# ModulCentralny.net
KiCad netlist of a schematic drawn in EAGLE
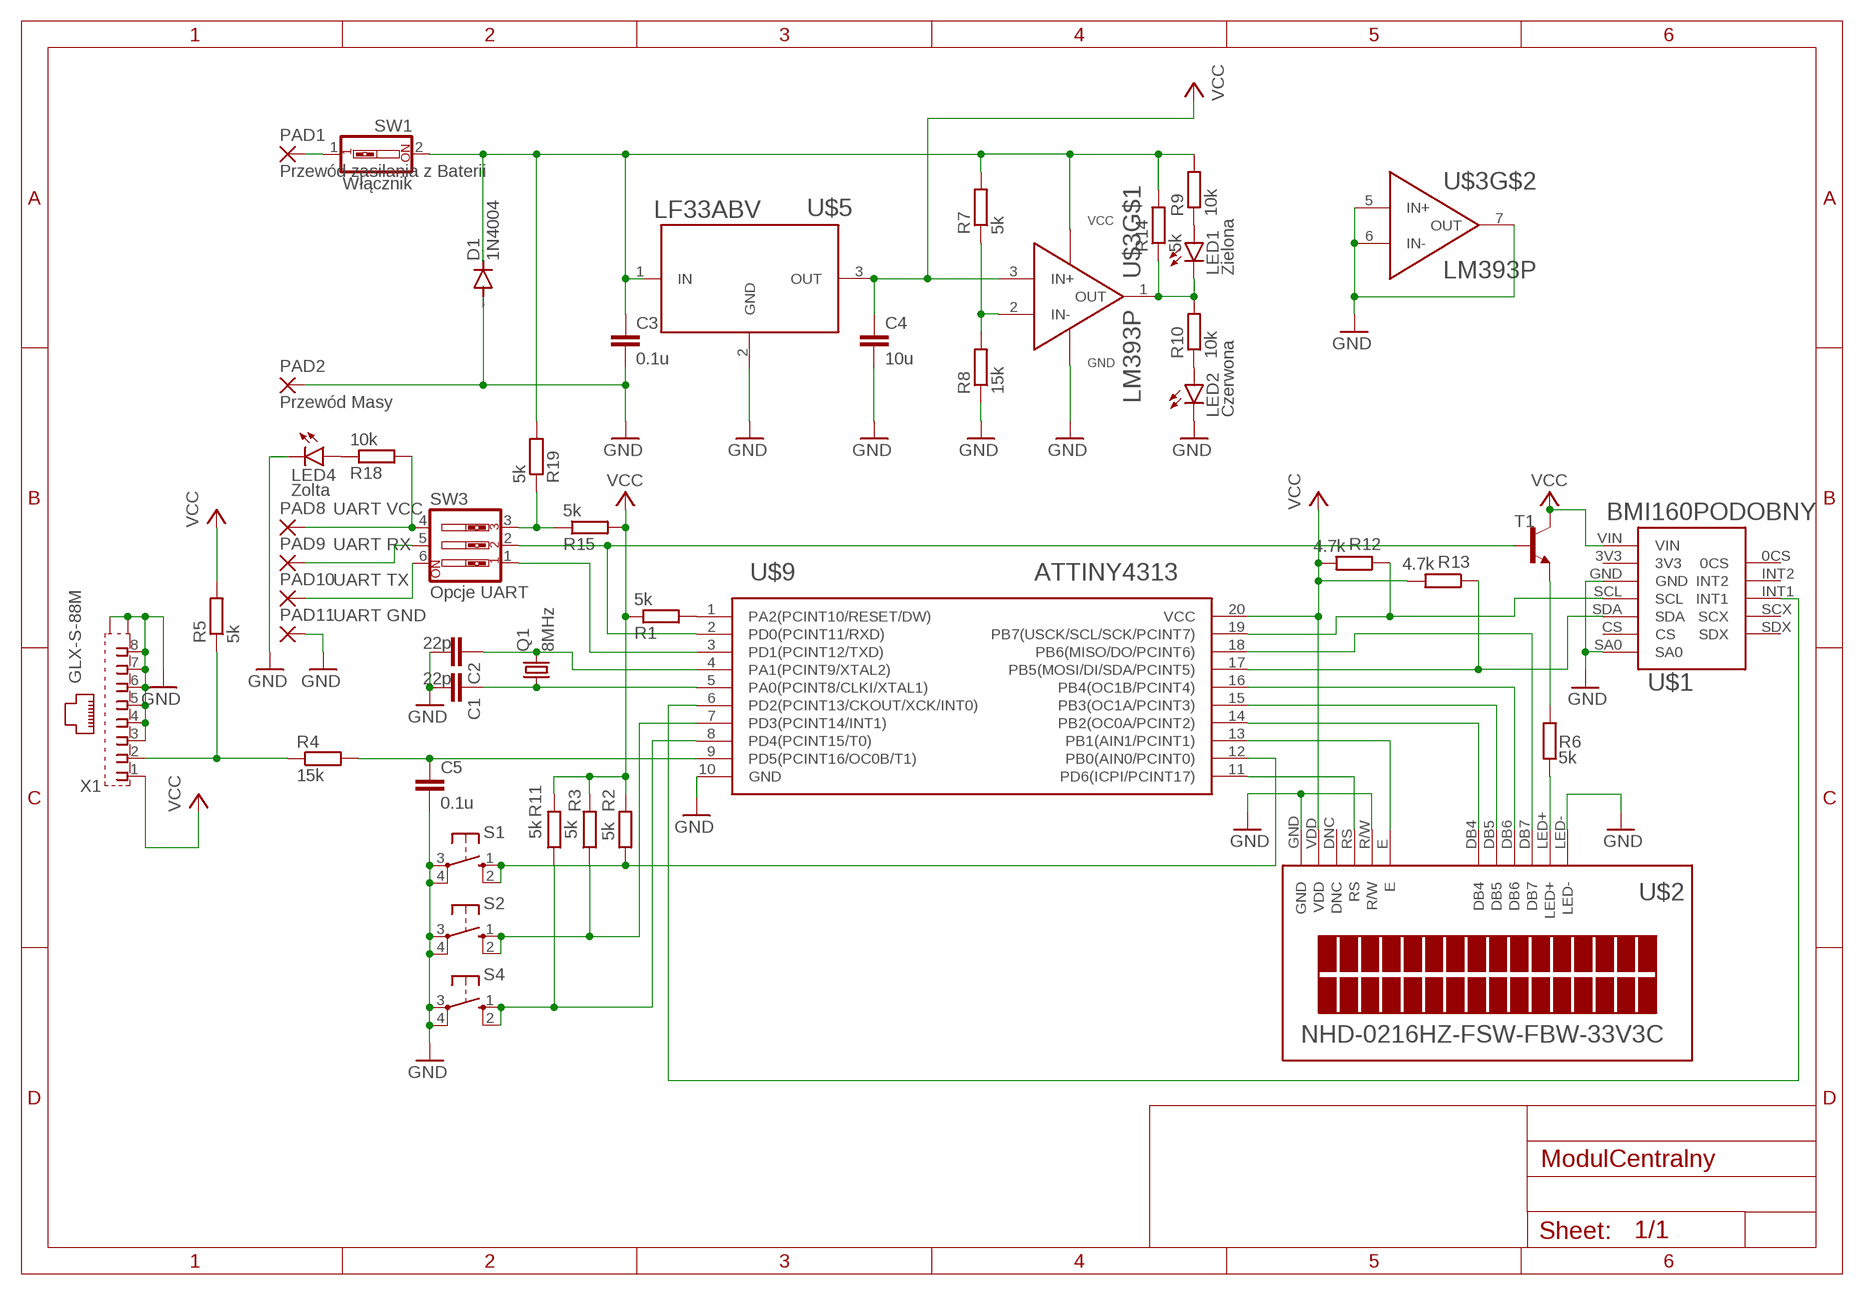
[diagram p0: schematic, sheet 1]

(export (version "E")
  (design (tool "Eeschema 10.0.6"))
  (components
    (comp (ref "C1")
      (value "22p")
      (footprint "eagle-import:C2.5-3")
      (libsource (lib "eagle-import") (part "C2,5-3"))
    )
    (comp (ref "C2")
      (value "22p")
      (footprint "eagle-import:C2.5-3")
      (libsource (lib "eagle-import") (part "C2,5-3"))
    )
    (comp (ref "C3")
      (value "0.1u")
      (footprint "eagle-import:C2.5-3")
      (libsource (lib "eagle-import") (part "C2,5-3"))
    )
    (comp (ref "C4")
      (value "10u")
      (footprint "eagle-import:C2.5-3")
      (libsource (lib "eagle-import") (part "C2,5-3"))
    )
    (comp (ref "C5")
      (value "0.1u")
      (footprint "eagle-import:C2.5-3")
      (libsource (lib "eagle-import") (part "C2,5-3"))
    )
    (comp (ref "D1")
      (value "1N4004")
      (footprint "eagle-import:DO41-10")
      (libsource (lib "eagle-import") (part "1N4004"))
    )
    (comp (ref "LED1")
      (value "Zielona")
      (footprint "eagle-import:LED5MM")
      (libsource (lib "eagle-import") (part "LED5MM"))
    )
    (comp (ref "LED2")
      (value "Czerwona")
      (footprint "eagle-import:LED5MM")
      (libsource (lib "eagle-import") (part "LED5MM"))
    )
    (comp (ref "LED4")
      (value "Zolta")
      (footprint "eagle-import:LED5MM")
      (libsource (lib "eagle-import") (part "LED5MM"))
    )
    (comp (ref "PAD1")
      (value "Przewód zasilania z Baterii")
      (footprint "eagle-import:2,54_1,1")
      (libsource (lib "eagle-import") (part "WIREPAD2,54/1,1"))
    )
    (comp (ref "PAD2")
      (value "Przewód Masy")
      (footprint "eagle-import:2,54_1,1")
      (libsource (lib "eagle-import") (part "WIREPAD2,54/1,1"))
    )
    (comp (ref "PAD8")
      (value "UART VCC")
      (footprint "eagle-import:3,17_1,3")
      (libsource (lib "eagle-import") (part "WIREPAD3,17/1,3"))
    )
    (comp (ref "PAD9")
      (value "UART RX")
      (footprint "eagle-import:3,17_1,3")
      (libsource (lib "eagle-import") (part "WIREPAD3,17/1,3"))
    )
    (comp (ref "PAD10")
      (value "UART TX")
      (footprint "eagle-import:3,17_1,3")
      (libsource (lib "eagle-import") (part "WIREPAD3,17/1,3"))
    )
    (comp (ref "PAD11")
      (value "UART GND")
      (footprint "eagle-import:3,17_1,3")
      (libsource (lib "eagle-import") (part "WIREPAD3,17/1,3"))
    )
    (comp (ref "Q1")
      (value "8MHz")
      (footprint "eagle-import:HC49U70")
      (libsource (lib "eagle-import") (part "CRYSTALHC49U70"))
    )
    (comp (ref "R1")
      (value "5k")
      (footprint "eagle-import:0207_7")
      (libsource (lib "eagle-import") (part "R-EU_0207/7"))
    )
    (comp (ref "R2")
      (value "5k")
      (footprint "eagle-import:0207_7")
      (libsource (lib "eagle-import") (part "R-EU_0207/7"))
    )
    (comp (ref "R3")
      (value "5k")
      (footprint "eagle-import:0207_7")
      (libsource (lib "eagle-import") (part "R-EU_0207/7"))
    )
    (comp (ref "R4")
      (value "15k")
      (footprint "eagle-import:0207_7")
      (libsource (lib "eagle-import") (part "R-EU_0207/7"))
    )
    (comp (ref "R5")
      (value "5k")
      (footprint "eagle-import:0207_7")
      (libsource (lib "eagle-import") (part "R-EU_0207/7"))
    )
    (comp (ref "R6")
      (value "5k")
      (footprint "eagle-import:0207_7")
      (libsource (lib "eagle-import") (part "R-EU_0207/7"))
    )
    (comp (ref "R7")
      (value "5k")
      (footprint "eagle-import:0207_7")
      (libsource (lib "eagle-import") (part "R-EU_0207/7"))
    )
    (comp (ref "R8")
      (value "15k")
      (footprint "eagle-import:0207_7")
      (libsource (lib "eagle-import") (part "R-EU_0207/7"))
    )
    (comp (ref "R9")
      (value "10k")
      (footprint "eagle-import:0207_7")
      (libsource (lib "eagle-import") (part "R-EU_0207/7"))
    )
    (comp (ref "R10")
      (value "10k")
      (footprint "eagle-import:0207_7")
      (libsource (lib "eagle-import") (part "R-EU_0207/7"))
    )
    (comp (ref "R11")
      (value "5k")
      (footprint "eagle-import:0207_7")
      (libsource (lib "eagle-import") (part "R-EU_0207/7"))
    )
    (comp (ref "R12")
      (value "4.7k")
      (footprint "eagle-import:0207_7")
      (libsource (lib "eagle-import") (part "R-EU_0207/7"))
    )
    (comp (ref "R13")
      (value "4.7k")
      (footprint "eagle-import:0207_7")
      (libsource (lib "eagle-import") (part "R-EU_0207/7"))
    )
    (comp (ref "R14")
      (value "5k")
      (footprint "eagle-import:0207_7")
      (libsource (lib "eagle-import") (part "R-EU_0207/7"))
    )
    (comp (ref "R15")
      (value "5k")
      (footprint "eagle-import:0207_7")
      (libsource (lib "eagle-import") (part "R-EU_0207/7"))
    )
    (comp (ref "R18")
      (value "10k")
      (footprint "eagle-import:0207_7")
      (libsource (lib "eagle-import") (part "R-EU_0207/7"))
    )
    (comp (ref "R19")
      (value "5k")
      (footprint "eagle-import:0207_7")
      (libsource (lib "eagle-import") (part "R-EU_0207/7"))
    )
    (comp (ref "S1")
      (value "10-XX")
      (footprint "eagle-import:B3F-10XX")
      (fields (field (name "MPN") "B3F-1000"))
      (libsource (lib "eagle-import") (part "10-XX"))
    )
    (comp (ref "S2")
      (value "10-XX")
      (footprint "eagle-import:B3F-10XX")
      (fields (field (name "MPN") "B3F-1000"))
      (libsource (lib "eagle-import") (part "10-XX"))
    )
    (comp (ref "S4")
      (value "10-XX")
      (footprint "eagle-import:B3F-10XX")
      (fields (field (name "MPN") "B3F-1000"))
      (libsource (lib "eagle-import") (part "10-XX"))
    )
    (comp (ref "SW1")
      (value "Włącznik")
      (footprint "eagle-import:EDG-01")
      (libsource (lib "eagle-import") (part "SW_DIP-1"))
    )
    (comp (ref "SW3")
      (value "Opcje UART")
      (footprint "eagle-import:EDG-03")
      (libsource (lib "eagle-import") (part "SW_DIP-3"))
    )
    (comp (ref "T1")
      (value "BC547B-NPN-TO92-CBE")
      (footprint "eagle-import:TO92-CBE")
      (libsource (lib "eagle-import") (part "-NPN-TO92-CBEBC547B"))
    )
    (comp (ref "U$1")
      (value "BMI160PODOBNY")
      (footprint "eagle-import:BMI160MODULE")
      (libsource (lib "eagle-import") (part "BMI160PODOBNY"))
    )
    (comp (ref "U$2")
      (value "NHD-0216HZ-FSW-FBW-33V3C")
      (footprint "eagle-import:NHD-0216HZ-FSW-FBW-33V3C")
      (libsource (lib "eagle-import") (part "NHD-0216HZ-FSW-FBW-33V3C"))
    )
    (comp (ref "U$3")
      (value "LM393P")
      (footprint "eagle-import:R-PDIP-T8")
      (libsource (lib "eagle-import") (part "LM393P"))
    )
    (comp (ref "U$5")
      (value "LF33ABV")
      (footprint "eagle-import:TO-220")
      (libsource (lib "eagle-import") (part "LF33ABV"))
    )
    (comp (ref "U$9")
      (value "ATTINY4313")
      (footprint "eagle-import:20P3")
      (libsource (lib "eagle-import") (part "ATTINY4313"))
    )
    (comp (ref "X1")
      (value "GLX-S-88M")
      (footprint "eagle-import:GLX-S-88M")
      (libsource (lib "eagle-import") (part "GLX-S-88M"))
    )
  )
  (nets
    (net (code "1") (name "GND") (class "Default")
      (node (ref "C1") (pin "2") (pinfunction "2_2") (pintype "passive"))
      (node (ref "C2") (pin "2") (pinfunction "2_2") (pintype "passive"))
      (node (ref "C3") (pin "2") (pinfunction "2_2") (pintype "passive"))
      (node (ref "C4") (pin "2") (pinfunction "2_2") (pintype "passive"))
      (node (ref "C5") (pin "2") (pinfunction "2_2") (pintype "passive"))
      (node (ref "D1") (pin "A") (pinfunction "A_A") (pintype "passive"))
      (node (ref "LED2") (pin "K") (pinfunction "C_K") (pintype "passive"))
      (node (ref "LED4") (pin "K") (pinfunction "C_K") (pintype "passive"))
      (node (ref "PAD11") (pin "1") (pinfunction "P_1") (pintype "passive"))
      (node (ref "PAD2") (pin "1") (pinfunction "P_1") (pintype "passive"))
      (node (ref "R8") (pin "1") (pinfunction "1_1") (pintype "passive"))
      (node (ref "S1") (pin "3") (pinfunction "P_3") (pintype "passive"))
      (node (ref "S1") (pin "4") (pinfunction "P1_4") (pintype "passive"))
      (node (ref "S2") (pin "3") (pinfunction "P_3") (pintype "passive"))
      (node (ref "S2") (pin "4") (pinfunction "P1_4") (pintype "passive"))
      (node (ref "S4") (pin "3") (pinfunction "P_3") (pintype "passive"))
      (node (ref "S4") (pin "4") (pinfunction "P1_4") (pintype "passive"))
      (node (ref "U$1") (pin "GND") (pinfunction "GND_GND") (pintype "bidirectional"))
      (node (ref "U$1") (pin "SA0") (pinfunction "SA0_SA0") (pintype "bidirectional"))
      (node (ref "U$2") (pin "GND") (pinfunction "GND_GND") (pintype "bidirectional"))
      (node (ref "U$2") (pin "LED-") (pinfunction "LED-_LED-") (pintype "bidirectional"))
      (node (ref "U$2") (pin "R/W") (pinfunction "R/W_R/W") (pintype "bidirectional"))
      (node (ref "U$3") (pin "4") (pinfunction "GND_4") (pintype "bidirectional"))
      (node (ref "U$3") (pin "5") (pinfunction "IN+_5") (pintype "input"))
      (node (ref "U$3") (pin "6") (pinfunction "IN-_6") (pintype "input"))
      (node (ref "U$3") (pin "7") (pinfunction "OUT_7") (pintype "bidirectional"))
      (node (ref "U$5") (pin "2") (pinfunction "GND_2") (pintype "bidirectional"))
      (node (ref "U$9") (pin "10") (pinfunction "GND_10") (pintype "bidirectional"))
      (node (ref "X1") (pin "3") (pinfunction "3_3") (pintype "passive"))
      (node (ref "X1") (pin "4") (pinfunction "4_4") (pintype "passive"))
      (node (ref "X1") (pin "5") (pinfunction "5_5") (pintype "passive"))
      (node (ref "X1") (pin "6") (pinfunction "6_6") (pintype "passive"))
      (node (ref "X1") (pin "7") (pinfunction "7_7") (pintype "passive"))
      (node (ref "X1") (pin "8") (pinfunction "8_8") (pintype "passive"))
      (node (ref "X1") (pin "S1") (pinfunction "S1_S1") (pintype "passive"))
      (node (ref "X1") (pin "S2") (pinfunction "S2_S2") (pintype "passive"))
    )
    (net (code "2") (name "Net-(LED1-C)") (class "Default")
      (node (ref "LED1") (pin "K") (pinfunction "C_K") (pintype "passive"))
      (node (ref "R10") (pin "2") (pinfunction "2_2") (pintype "passive"))
      (node (ref "R14") (pin "1") (pinfunction "1_1") (pintype "passive"))
      (node (ref "U$3") (pin "1") (pinfunction "OUT_1") (pintype "bidirectional"))
    )
    (net (code "3") (name "Net-(LED1-PadA)") (class "Default")
      (node (ref "LED1") (pin "A") (pinfunction "A_A") (pintype "passive"))
      (node (ref "R9") (pin "1") (pinfunction "1_1") (pintype "passive"))
    )
    (net (code "4") (name "Net-(LED2-PadA)") (class "Default")
      (node (ref "LED2") (pin "A") (pinfunction "A_A") (pintype "passive"))
      (node (ref "R10") (pin "1") (pinfunction "1_1") (pintype "passive"))
    )
    (net (code "5") (name "Net-(LED4-PadA)") (class "Default")
      (node (ref "LED4") (pin "A") (pinfunction "A_A") (pintype "passive"))
      (node (ref "R18") (pin "1") (pinfunction "1_1") (pintype "passive"))
    )
    (net (code "6") (name "Net-(PAD1-P)") (class "Default")
      (node (ref "PAD1") (pin "1") (pinfunction "P_1") (pintype "passive"))
      (node (ref "SW1") (pin "1") (pinfunction "1_1") (pintype "passive"))
    )
    (net (code "7") (name "Net-(PAD8-P)") (class "Default")
      (node (ref "PAD8") (pin "1") (pinfunction "P_1") (pintype "passive"))
      (node (ref "R18") (pin "2") (pinfunction "2_2") (pintype "passive"))
      (node (ref "SW3") (pin "4") (pinfunction "4_4") (pintype "passive"))
    )
    (net (code "8") (name "Net-(PAD9-P)") (class "Default")
      (node (ref "PAD9") (pin "1") (pinfunction "P_1") (pintype "passive"))
      (node (ref "SW3") (pin "5") (pinfunction "5_5") (pintype "passive"))
    )
    (net (code "9") (name "Net-(PAD10-P)") (class "Default")
      (node (ref "PAD10") (pin "1") (pinfunction "P_1") (pintype "passive"))
      (node (ref "SW3") (pin "6") (pinfunction "6_6") (pintype "passive"))
    )
    (net (code "10") (name "Net-(R4-Pad1)") (class "Default")
      (node (ref "R4") (pin "1") (pinfunction "1_1") (pintype "passive"))
      (node (ref "R5") (pin "1") (pinfunction "1_1") (pintype "passive"))
      (node (ref "X1") (pin "2") (pinfunction "2_2") (pintype "passive"))
    )
    (net (code "11") (name "Net-(R6-Pad1)") (class "Default")
      (node (ref "R6") (pin "1") (pinfunction "1_1") (pintype "passive"))
      (node (ref "T1") (pin "E") (pinfunction "E_E") (pintype "passive"))
    )
    (net (code "12") (name "Net-(R6-Pad2)") (class "Default")
      (node (ref "R6") (pin "2") (pinfunction "2_2") (pintype "passive"))
      (node (ref "U$2") (pin "LED+") (pinfunction "LED+_LED+") (pintype "bidirectional"))
    )
    (net (code "13") (name "Net-(R15-Pad1)") (class "Default")
      (node (ref "R15") (pin "1") (pinfunction "1_1") (pintype "passive"))
      (node (ref "R19") (pin "1") (pinfunction "1_1") (pintype "passive"))
      (node (ref "SW3") (pin "3") (pinfunction "3_3") (pintype "passive"))
    )
    (net (code "14") (name "Net-(S1-S)") (class "Default")
      (node (ref "R2") (pin "1") (pinfunction "1_1") (pintype "passive"))
      (node (ref "S1") (pin "1") (pinfunction "S_1") (pintype "passive"))
      (node (ref "S1") (pin "2") (pinfunction "S1_2") (pintype "passive"))
      (node (ref "U$9") (pin "12") (pinfunction "PB0(AIN0/PCINT0)_12") (pintype "bidirectional"))
    )
    (net (code "15") (name "Net-(S2-S)") (class "Default")
      (node (ref "R3") (pin "1") (pinfunction "1_1") (pintype "passive"))
      (node (ref "S2") (pin "1") (pinfunction "S_1") (pintype "passive"))
      (node (ref "S2") (pin "2") (pinfunction "S1_2") (pintype "passive"))
      (node (ref "U$9") (pin "7") (pinfunction "PD3(PCINT14/INT1)_7") (pintype "bidirectional"))
    )
    (net (code "16") (name "Net-(S4-S)") (class "Default")
      (node (ref "R11") (pin "1") (pinfunction "1_1") (pintype "passive"))
      (node (ref "S4") (pin "1") (pinfunction "S_1") (pintype "passive"))
      (node (ref "S4") (pin "2") (pinfunction "S1_2") (pintype "passive"))
      (node (ref "U$9") (pin "8") (pinfunction "PD4(PCINT15/T0)_8") (pintype "bidirectional"))
    )
    (net (code "17") (name "Net-(U$3A-IN-)") (class "Default")
      (node (ref "R7") (pin "1") (pinfunction "1_1") (pintype "passive"))
      (node (ref "R8") (pin "2") (pinfunction "2_2") (pintype "passive"))
      (node (ref "U$3") (pin "2") (pinfunction "IN-_2") (pintype "input"))
    )
    (net (code "18") (name "Net-(U$3A-VCC)") (class "Default")
      (node (ref "C3") (pin "1") (pinfunction "1_1") (pintype "passive"))
      (node (ref "D1") (pin "C") (pinfunction "C_C") (pintype "passive"))
      (node (ref "R14") (pin "2") (pinfunction "2_2") (pintype "passive"))
      (node (ref "R19") (pin "2") (pinfunction "2_2") (pintype "passive"))
      (node (ref "R7") (pin "2") (pinfunction "2_2") (pintype "passive"))
      (node (ref "R9") (pin "2") (pinfunction "2_2") (pintype "passive"))
      (node (ref "SW1") (pin "2") (pinfunction "2_2") (pintype "passive"))
      (node (ref "U$3") (pin "8") (pinfunction "VCC_8") (pintype "bidirectional"))
      (node (ref "U$5") (pin "1") (pinfunction "IN_1") (pintype "input"))
    )
    (net (code "19") (name "Net-(U$9-PA0(PCINT8{slash}CLKI{slash}XTAL1))") (class "Default")
      (node (ref "C1") (pin "1") (pinfunction "1_1") (pintype "passive"))
      (node (ref "Q1") (pin "1") (pinfunction "1_1") (pintype "passive"))
      (node (ref "U$9") (pin "5") (pinfunction "PA0(PCINT8/CLKI/XTAL1)_5") (pintype "bidirectional"))
    )
    (net (code "20") (name "Net-(U$9-PA1(PCINT9{slash}XTAL2))") (class "Default")
      (node (ref "C2") (pin "1") (pinfunction "1_1") (pintype "passive"))
      (node (ref "Q1") (pin "2") (pinfunction "2_2") (pintype "passive"))
      (node (ref "U$9") (pin "4") (pinfunction "PA1(PCINT9/XTAL2)_4") (pintype "bidirectional"))
    )
    (net (code "21") (name "Net-(U$9-PA2(PCINT10{slash}RESET{slash}DW))") (class "Default")
      (node (ref "R1") (pin "2") (pinfunction "2_2") (pintype "passive"))
      (node (ref "U$9") (pin "1") (pinfunction "PA2(PCINT10/RESET/DW)_1") (pintype "bidirectional"))
    )
    (net (code "22") (name "Net-(U$9-PB1(AIN1{slash}PCINT1))") (class "Default")
      (node (ref "U$2") (pin "E") (pinfunction "E_E") (pintype "bidirectional"))
      (node (ref "U$9") (pin "13") (pinfunction "PB1(AIN1/PCINT1)_13") (pintype "bidirectional"))
    )
    (net (code "23") (name "Net-(U$9-PB2(OC0A{slash}PCINT2))") (class "Default")
      (node (ref "U$2") (pin "DB4") (pinfunction "DB4_DB4") (pintype "bidirectional"))
      (node (ref "U$9") (pin "14") (pinfunction "PB2(OC0A/PCINT2)_14") (pintype "bidirectional"))
    )
    (net (code "24") (name "Net-(U$9-PB3(OC1A{slash}PCINT3))") (class "Default")
      (node (ref "U$2") (pin "DB5") (pinfunction "DB5_DB5") (pintype "bidirectional"))
      (node (ref "U$9") (pin "15") (pinfunction "PB3(OC1A/PCINT3)_15") (pintype "bidirectional"))
    )
    (net (code "25") (name "Net-(U$9-PB4(OC1B{slash}PCINT4))") (class "Default")
      (node (ref "U$2") (pin "DB6") (pinfunction "DB6_DB6") (pintype "bidirectional"))
      (node (ref "U$9") (pin "16") (pinfunction "PB4(OC1B/PCINT4)_16") (pintype "bidirectional"))
    )
    (net (code "26") (name "Net-(U$9-PB5(MOSI{slash}DI{slash}SDA{slash}PCINT5))") (class "Default")
      (node (ref "R13") (pin "1") (pinfunction "1_1") (pintype "passive"))
      (node (ref "U$1") (pin "SDA") (pinfunction "SDA_SDA") (pintype "bidirectional"))
      (node (ref "U$9") (pin "17") (pinfunction "PB5(MOSI/DI/SDA/PCINT5)_17") (pintype "bidirectional"))
    )
    (net (code "27") (name "Net-(U$9-PB6(MISO{slash}DO{slash}PCINT6))") (class "Default")
      (node (ref "U$2") (pin "DB7") (pinfunction "DB7_DB7") (pintype "bidirectional"))
      (node (ref "U$9") (pin "18") (pinfunction "PB6(MISO/DO/PCINT6)_18") (pintype "bidirectional"))
    )
    (net (code "28") (name "Net-(U$9-PB7(USCK{slash}SCL{slash}SCK{slash}PCINT7))") (class "Default")
      (node (ref "R12") (pin "1") (pinfunction "1_1") (pintype "passive"))
      (node (ref "U$1") (pin "SCL") (pinfunction "SCL_SCL") (pintype "bidirectional"))
      (node (ref "U$9") (pin "19") (pinfunction "PB7(USCK/SCL/SCK/PCINT7)_19") (pintype "bidirectional"))
    )
    (net (code "29") (name "Net-(U$9-PD0(PCINT11{slash}RXD))") (class "Default")
      (node (ref "SW3") (pin "2") (pinfunction "2_2") (pintype "passive"))
      (node (ref "T1") (pin "B") (pinfunction "B_B") (pintype "passive"))
      (node (ref "U$9") (pin "2") (pinfunction "PD0(PCINT11/RXD)_2") (pintype "bidirectional"))
    )
    (net (code "30") (name "Net-(U$9-PD1(PCINT12{slash}TXD))") (class "Default")
      (node (ref "SW3") (pin "1") (pinfunction "1_1") (pintype "passive"))
      (node (ref "U$9") (pin "3") (pinfunction "PD1(PCINT12/TXD)_3") (pintype "bidirectional"))
    )
    (net (code "31") (name "Net-(U$9-PD2(PCINT13{slash}CKOUT{slash}XCK{slash}INT0))") (class "Default")
      (node (ref "U$1") (pin "INT1") (pinfunction "INT1_INT1") (pintype "bidirectional"))
      (node (ref "U$9") (pin "6") (pinfunction "PD2(PCINT13/CKOUT/XCK/INT0)_6") (pintype "bidirectional"))
    )
    (net (code "32") (name "Net-(U$9-PD5(PCINT16{slash}OC0B{slash}T1))") (class "Default")
      (node (ref "C5") (pin "1") (pinfunction "1_1") (pintype "passive"))
      (node (ref "R4") (pin "2") (pinfunction "2_2") (pintype "passive"))
      (node (ref "U$9") (pin "9") (pinfunction "PD5(PCINT16/OC0B/T1)_9") (pintype "bidirectional"))
    )
    (net (code "33") (name "Net-(U$9-PD6(ICPI{slash}PCINT17))") (class "Default")
      (node (ref "U$2") (pin "RS") (pinfunction "RS_RS") (pintype "bidirectional"))
      (node (ref "U$9") (pin "11") (pinfunction "PD6(ICPI/PCINT17)_11") (pintype "bidirectional"))
    )
    (net (code "34") (name "VCC") (class "Default")
      (node (ref "C4") (pin "1") (pinfunction "1_1") (pintype "passive"))
      (node (ref "R1") (pin "1") (pinfunction "1_1") (pintype "passive"))
      (node (ref "R11") (pin "2") (pinfunction "2_2") (pintype "passive"))
      (node (ref "R12") (pin "2") (pinfunction "2_2") (pintype "passive"))
      (node (ref "R13") (pin "2") (pinfunction "2_2") (pintype "passive"))
      (node (ref "R15") (pin "2") (pinfunction "2_2") (pintype "passive"))
      (node (ref "R2") (pin "2") (pinfunction "2_2") (pintype "passive"))
      (node (ref "R3") (pin "2") (pinfunction "2_2") (pintype "passive"))
      (node (ref "R5") (pin "2") (pinfunction "2_2") (pintype "passive"))
      (node (ref "T1") (pin "C") (pinfunction "C_C") (pintype "passive"))
      (node (ref "U$1") (pin "VIN") (pinfunction "VIN_VIN") (pintype "bidirectional"))
      (node (ref "U$2") (pin "VDD") (pinfunction "VDD_VDD") (pintype "bidirectional"))
      (node (ref "U$3") (pin "3") (pinfunction "IN+_3") (pintype "input"))
      (node (ref "U$5") (pin "3") (pinfunction "OUT_3") (pintype "output"))
      (node (ref "U$9") (pin "20") (pinfunction "VCC_20") (pintype "bidirectional"))
      (node (ref "X1") (pin "1") (pinfunction "1_1") (pintype "passive"))
    )
    (net (code "35") (name "unconnected-(U$1-Pad0CS)") (class "Default")
      (node (ref "U$1") (pin "0CS") (pinfunction "0CS_0CS") (pintype "bidirectional"))
    )
    (net (code "36") (name "unconnected-(U$1-Pad3V3)") (class "Default")
      (node (ref "U$1") (pin "3V3") (pinfunction "3V3_3V3") (pintype "bidirectional"))
    )
    (net (code "37") (name "unconnected-(U$1-PadCS)") (class "Default")
      (node (ref "U$1") (pin "CS") (pinfunction "CS_CS") (pintype "bidirectional"))
    )
    (net (code "38") (name "unconnected-(U$1-PadINT2)") (class "Default")
      (node (ref "U$1") (pin "INT2") (pinfunction "INT2_INT2") (pintype "bidirectional"))
    )
    (net (code "39") (name "unconnected-(U$1-PadSCX)") (class "Default")
      (node (ref "U$1") (pin "SCX") (pinfunction "SCX_SCX") (pintype "bidirectional"))
    )
    (net (code "40") (name "unconnected-(U$1-PadSDX)") (class "Default")
      (node (ref "U$1") (pin "SDX") (pinfunction "SDX_SDX") (pintype "bidirectional"))
    )
    (net (code "41") (name "unconnected-(U$2-PadDNC)") (class "Default")
      (node (ref "U$2") (pin "DNC") (pinfunction "DNC_DNC") (pintype "bidirectional"))
    )
  )
)
